# 1-Schematic_mixmult.net
KiCad netlist of a schematic drawn in EasyEDA
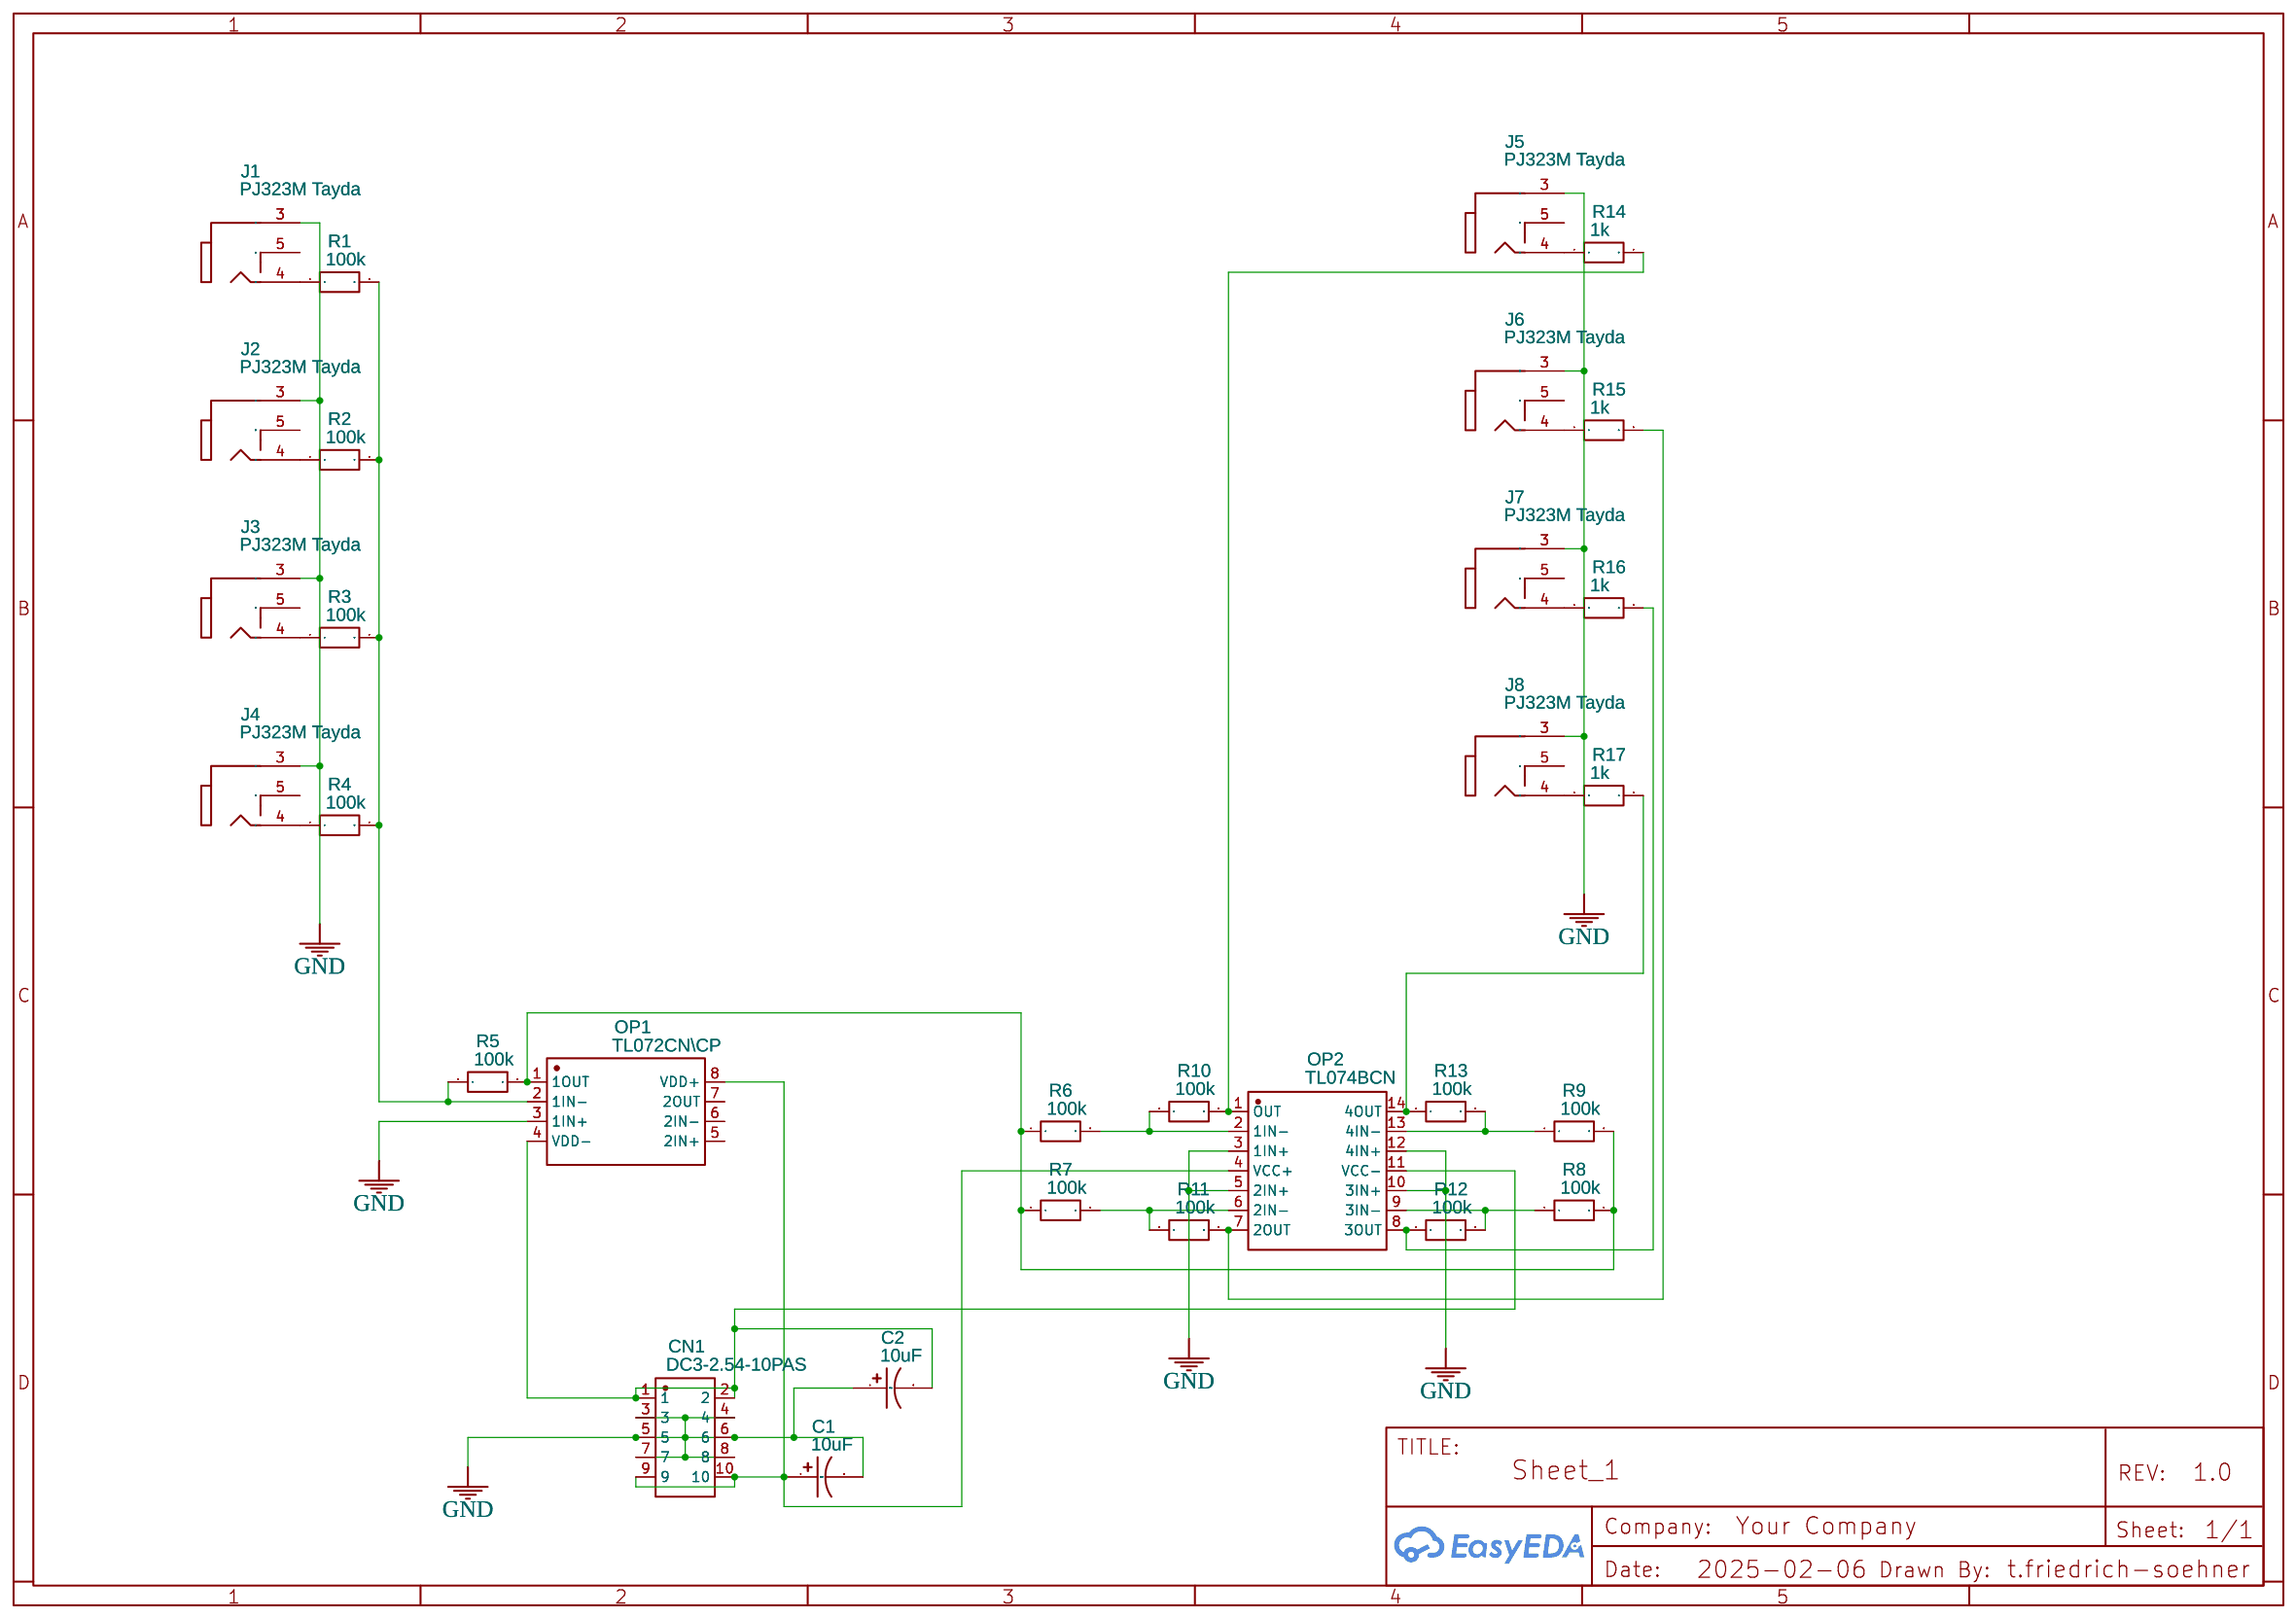
[diagram p0: schematic sheet]

(export (version "E")
  (design (tool "Eeschema 10.0.6"))
  (components
    (comp (ref "C1")
      (value "10uF")
      (fields
        (field (name "Manufacturer Part") "50MS710MEFCTZ5X7")
        (field (name "Manufacturer") "rubycon(红宝石)")
      )
      (libsource (lib "") (part "50MS710MEFCTZ5X7"))
    )
    (comp (ref "C2")
      (value "10uF")
      (fields
        (field (name "Manufacturer Part") "50MS710MEFCTZ5X7")
        (field (name "Manufacturer") "rubycon(红宝石)")
      )
      (libsource (lib "") (part "50MS710MEFCTZ5X7"))
    )
    (comp (ref "CN1")
      (value "DC3-2.54-10PAS")
      (fields (field (name "Manufacturer") "ZHOURI(洲日)"))
      (libsource (lib "") (part "DC3-2.54-10PAS"))
    )
    (comp (ref "J1") (value "PJ323M Tayda") (libsource (lib "") (part "PJ323M Tayda")))
    (comp (ref "J2") (value "PJ323M Tayda") (libsource (lib "") (part "PJ323M Tayda")))
    (comp (ref "J3") (value "PJ323M Tayda") (libsource (lib "") (part "PJ323M Tayda")))
    (comp (ref "J4") (value "PJ323M Tayda") (libsource (lib "") (part "PJ323M Tayda")))
    (comp (ref "J5") (value "PJ323M Tayda") (libsource (lib "") (part "PJ323M Tayda")))
    (comp (ref "J6") (value "PJ323M Tayda") (libsource (lib "") (part "PJ323M Tayda")))
    (comp (ref "J7") (value "PJ323M Tayda") (libsource (lib "") (part "PJ323M Tayda")))
    (comp (ref "J8") (value "PJ323M Tayda") (libsource (lib "") (part "PJ323M Tayda")))
    (comp (ref "OP1") (value "TL072CN\\CP") (libsource (lib "") (part "TL072CD")))
    (comp (ref "OP2")
      (value "TL074BCN")
      (fields (field (name "Manufacturer") "TI(德州仪器)"))
      (libsource (lib "") (part "TL074BCN"))
    )
    (comp (ref "R1") (value "100k") (libsource (lib "") (part "Res_AXIAL-0.4(1/4W)_US")))
    (comp (ref "R2") (value "100k") (libsource (lib "") (part "Res_AXIAL-0.4(1/4W)_US")))
    (comp (ref "R3") (value "100k") (libsource (lib "") (part "Res_AXIAL-0.4(1/4W)_US")))
    (comp (ref "R4") (value "100k") (libsource (lib "") (part "Res_AXIAL-0.4(1/4W)_US")))
    (comp (ref "R5") (value "100k") (libsource (lib "") (part "Res_AXIAL-0.4(1/4W)_US")))
    (comp (ref "R6") (value "100k") (libsource (lib "") (part "Res_AXIAL-0.4(1/4W)_US")))
    (comp (ref "R7") (value "100k") (libsource (lib "") (part "Res_AXIAL-0.4(1/4W)_US")))
    (comp (ref "R8") (value "100k") (libsource (lib "") (part "Res_AXIAL-0.4(1/4W)_US")))
    (comp (ref "R9") (value "100k") (libsource (lib "") (part "Res_AXIAL-0.4(1/4W)_US")))
    (comp (ref "R10") (value "100k") (libsource (lib "") (part "Res_AXIAL-0.4(1/4W)_US")))
    (comp (ref "R11") (value "100k") (libsource (lib "") (part "Res_AXIAL-0.4(1/4W)_US")))
    (comp (ref "R12") (value "100k") (libsource (lib "") (part "Res_AXIAL-0.4(1/4W)_US")))
    (comp (ref "R13") (value "100k") (libsource (lib "") (part "Res_AXIAL-0.4(1/4W)_US")))
    (comp (ref "R14") (value "1k") (libsource (lib "") (part "Res_AXIAL-0.4(1/4W)_US")))
    (comp (ref "R15") (value "1k") (libsource (lib "") (part "Res_AXIAL-0.4(1/4W)_US")))
    (comp (ref "R16") (value "1k") (libsource (lib "") (part "Res_AXIAL-0.4(1/4W)_US")))
    (comp (ref "R17") (value "1k") (libsource (lib "") (part "Res_AXIAL-0.4(1/4W)_US")))
  )
  (nets
    (net (code "1") (name "GND") (class "Default")
      (node (ref "C1") (pin "2") (pinfunction "2_2") (pintype "unspecified"))
      (node (ref "C2") (pin "1") (pinfunction "1_1") (pintype "unspecified"))
      (node (ref "CN1") (pin "3") (pinfunction "3_3") (pintype "unspecified"))
      (node (ref "CN1") (pin "4") (pinfunction "4_4") (pintype "unspecified"))
      (node (ref "CN1") (pin "5") (pinfunction "5_5") (pintype "unspecified"))
      (node (ref "CN1") (pin "6") (pinfunction "6_6") (pintype "unspecified"))
      (node (ref "CN1") (pin "7") (pinfunction "7_7") (pintype "unspecified"))
      (node (ref "CN1") (pin "8") (pinfunction "8_8") (pintype "unspecified"))
      (node (ref "J1") (pin "3") (pinfunction "3_3") (pintype "unspecified"))
      (node (ref "J2") (pin "3") (pinfunction "3_3") (pintype "unspecified"))
      (node (ref "J3") (pin "3") (pinfunction "3_3") (pintype "unspecified"))
      (node (ref "J4") (pin "3") (pinfunction "3_3") (pintype "unspecified"))
      (node (ref "J5") (pin "3") (pinfunction "3_3") (pintype "unspecified"))
      (node (ref "J6") (pin "3") (pinfunction "3_3") (pintype "unspecified"))
      (node (ref "J7") (pin "3") (pinfunction "3_3") (pintype "unspecified"))
      (node (ref "J8") (pin "3") (pinfunction "3_3") (pintype "unspecified"))
      (node (ref "OP1") (pin "3") (pinfunction "1IN+_3") (pintype "unspecified"))
      (node (ref "OP2") (pin "10") (pinfunction "3IN+_10") (pintype "unspecified"))
      (node (ref "OP2") (pin "12") (pinfunction "4IN+_12") (pintype "unspecified"))
      (node (ref "OP2") (pin "3") (pinfunction "1IN+_3") (pintype "unspecified"))
      (node (ref "OP2") (pin "5") (pinfunction "2IN+_5") (pintype "unspecified"))
    )
    (net (code "2") (name "Net-(J1-Pad4)") (class "Default")
      (node (ref "J1") (pin "4") (pinfunction "4_4") (pintype "unspecified"))
      (node (ref "R1") (pin "1") (pinfunction "1_1") (pintype "unspecified"))
    )
    (net (code "3") (name "Net-(J2-Pad4)") (class "Default")
      (node (ref "J2") (pin "4") (pinfunction "4_4") (pintype "unspecified"))
      (node (ref "R2") (pin "1") (pinfunction "1_1") (pintype "unspecified"))
    )
    (net (code "4") (name "Net-(J3-Pad4)") (class "Default")
      (node (ref "J3") (pin "4") (pinfunction "4_4") (pintype "unspecified"))
      (node (ref "R3") (pin "1") (pinfunction "1_1") (pintype "unspecified"))
    )
    (net (code "5") (name "Net-(J4-Pad4)") (class "Default")
      (node (ref "J4") (pin "4") (pinfunction "4_4") (pintype "unspecified"))
      (node (ref "R4") (pin "1") (pinfunction "1_1") (pintype "unspecified"))
    )
    (net (code "6") (name "Net-(J5-Pad4)") (class "Default")
      (node (ref "J5") (pin "4") (pinfunction "4_4") (pintype "unspecified"))
      (node (ref "R14") (pin "1") (pinfunction "1_1") (pintype "unspecified"))
    )
    (net (code "7") (name "Net-(J6-Pad4)") (class "Default")
      (node (ref "J6") (pin "4") (pinfunction "4_4") (pintype "unspecified"))
      (node (ref "R15") (pin "1") (pinfunction "1_1") (pintype "unspecified"))
    )
    (net (code "8") (name "Net-(J7-Pad4)") (class "Default")
      (node (ref "J7") (pin "4") (pinfunction "4_4") (pintype "unspecified"))
      (node (ref "R16") (pin "1") (pinfunction "1_1") (pintype "unspecified"))
    )
    (net (code "9") (name "Net-(J8-Pad4)") (class "Default")
      (node (ref "J8") (pin "4") (pinfunction "4_4") (pintype "unspecified"))
      (node (ref "R17") (pin "1") (pinfunction "1_1") (pintype "unspecified"))
    )
    (net (code "10") (name "Net-(OP1-1IN-)") (class "Default")
      (node (ref "OP1") (pin "2") (pinfunction "1IN-_2") (pintype "unspecified"))
      (node (ref "R1") (pin "2") (pinfunction "2_2") (pintype "unspecified"))
      (node (ref "R2") (pin "2") (pinfunction "2_2") (pintype "unspecified"))
      (node (ref "R3") (pin "2") (pinfunction "2_2") (pintype "unspecified"))
      (node (ref "R4") (pin "2") (pinfunction "2_2") (pintype "unspecified"))
      (node (ref "R5") (pin "1") (pinfunction "1_1") (pintype "unspecified"))
    )
    (net (code "11") (name "Net-(OP1-1OUT)") (class "Default")
      (node (ref "OP1") (pin "1") (pinfunction "1OUT_1") (pintype "unspecified"))
      (node (ref "R5") (pin "2") (pinfunction "2_2") (pintype "unspecified"))
      (node (ref "R6") (pin "1") (pinfunction "1_1") (pintype "unspecified"))
      (node (ref "R7") (pin "1") (pinfunction "1_1") (pintype "unspecified"))
      (node (ref "R8") (pin "2") (pinfunction "2_2") (pintype "unspecified"))
      (node (ref "R9") (pin "2") (pinfunction "2_2") (pintype "unspecified"))
    )
    (net (code "12") (name "Net-(OP1-VDD+)") (class "Default")
      (node (ref "C1") (pin "1") (pinfunction "1_1") (pintype "unspecified"))
      (node (ref "CN1") (pin "10") (pinfunction "10_10") (pintype "unspecified"))
      (node (ref "CN1") (pin "9") (pinfunction "9_9") (pintype "unspecified"))
      (node (ref "OP1") (pin "8") (pinfunction "VDD+_8") (pintype "unspecified"))
      (node (ref "OP2") (pin "4") (pinfunction "VCC+_4") (pintype "unspecified"))
    )
    (net (code "13") (name "Net-(OP1-VDD-)") (class "Default")
      (node (ref "C2") (pin "2") (pinfunction "2_2") (pintype "unspecified"))
      (node (ref "CN1") (pin "1") (pinfunction "1_1") (pintype "unspecified"))
      (node (ref "CN1") (pin "2") (pinfunction "2_2") (pintype "unspecified"))
      (node (ref "OP1") (pin "4") (pinfunction "VDD-_4") (pintype "unspecified"))
      (node (ref "OP2") (pin "11") (pinfunction "VCC-_11") (pintype "unspecified"))
    )
    (net (code "14") (name "Net-(OP2-1IN-)") (class "Default")
      (node (ref "OP2") (pin "2") (pinfunction "1IN-_2") (pintype "unspecified"))
      (node (ref "R10") (pin "1") (pinfunction "1_1") (pintype "unspecified"))
      (node (ref "R6") (pin "2") (pinfunction "2_2") (pintype "unspecified"))
    )
    (net (code "15") (name "Net-(OP2-2IN-)") (class "Default")
      (node (ref "OP2") (pin "6") (pinfunction "2IN-_6") (pintype "unspecified"))
      (node (ref "R11") (pin "1") (pinfunction "1_1") (pintype "unspecified"))
      (node (ref "R7") (pin "2") (pinfunction "2_2") (pintype "unspecified"))
    )
    (net (code "16") (name "Net-(OP2-2OUT)") (class "Default")
      (node (ref "OP2") (pin "7") (pinfunction "2OUT_7") (pintype "unspecified"))
      (node (ref "R11") (pin "2") (pinfunction "2_2") (pintype "unspecified"))
      (node (ref "R15") (pin "2") (pinfunction "2_2") (pintype "unspecified"))
    )
    (net (code "17") (name "Net-(OP2-3IN-)") (class "Default")
      (node (ref "OP2") (pin "9") (pinfunction "3IN-_9") (pintype "unspecified"))
      (node (ref "R12") (pin "2") (pinfunction "2_2") (pintype "unspecified"))
      (node (ref "R8") (pin "1") (pinfunction "1_1") (pintype "unspecified"))
    )
    (net (code "18") (name "Net-(OP2-3OUT)") (class "Default")
      (node (ref "OP2") (pin "8") (pinfunction "3OUT_8") (pintype "unspecified"))
      (node (ref "R12") (pin "1") (pinfunction "1_1") (pintype "unspecified"))
      (node (ref "R16") (pin "2") (pinfunction "2_2") (pintype "unspecified"))
    )
    (net (code "19") (name "Net-(OP2-4IN-)") (class "Default")
      (node (ref "OP2") (pin "13") (pinfunction "4IN-_13") (pintype "unspecified"))
      (node (ref "R13") (pin "2") (pinfunction "2_2") (pintype "unspecified"))
      (node (ref "R9") (pin "1") (pinfunction "1_1") (pintype "unspecified"))
    )
    (net (code "20") (name "Net-(OP2-4OUT)") (class "Default")
      (node (ref "OP2") (pin "14") (pinfunction "4OUT_14") (pintype "unspecified"))
      (node (ref "R13") (pin "1") (pinfunction "1_1") (pintype "unspecified"))
      (node (ref "R17") (pin "2") (pinfunction "2_2") (pintype "unspecified"))
    )
    (net (code "21") (name "Net-(OP2-OUT)") (class "Default")
      (node (ref "OP2") (pin "1") (pinfunction "OUT_1") (pintype "unspecified"))
      (node (ref "R10") (pin "2") (pinfunction "2_2") (pintype "unspecified"))
      (node (ref "R14") (pin "2") (pinfunction "2_2") (pintype "unspecified"))
    )
    (net (code "22") (name "unconnected-(J1-Pad5)") (class "Default")
      (node (ref "J1") (pin "5") (pinfunction "5_5") (pintype "unspecified"))
    )
    (net (code "23") (name "unconnected-(J2-Pad5)") (class "Default")
      (node (ref "J2") (pin "5") (pinfunction "5_5") (pintype "unspecified"))
    )
    (net (code "24") (name "unconnected-(J3-Pad5)") (class "Default")
      (node (ref "J3") (pin "5") (pinfunction "5_5") (pintype "unspecified"))
    )
    (net (code "25") (name "unconnected-(J4-Pad5)") (class "Default")
      (node (ref "J4") (pin "5") (pinfunction "5_5") (pintype "unspecified"))
    )
    (net (code "26") (name "unconnected-(J5-Pad5)") (class "Default")
      (node (ref "J5") (pin "5") (pinfunction "5_5") (pintype "unspecified"))
    )
    (net (code "27") (name "unconnected-(J6-Pad5)") (class "Default")
      (node (ref "J6") (pin "5") (pinfunction "5_5") (pintype "unspecified"))
    )
    (net (code "28") (name "unconnected-(J7-Pad5)") (class "Default")
      (node (ref "J7") (pin "5") (pinfunction "5_5") (pintype "unspecified"))
    )
    (net (code "29") (name "unconnected-(J8-Pad5)") (class "Default")
      (node (ref "J8") (pin "5") (pinfunction "5_5") (pintype "unspecified"))
    )
    (net (code "30") (name "unconnected-(OP1-2IN+-Pad5)") (class "Default")
      (node (ref "OP1") (pin "5") (pinfunction "2IN+_5") (pintype "unspecified"))
    )
    (net (code "31") (name "unconnected-(OP1-2IN--Pad6)") (class "Default")
      (node (ref "OP1") (pin "6") (pinfunction "2IN-_6") (pintype "unspecified"))
    )
    (net (code "32") (name "unconnected-(OP1-2OUT-Pad7)") (class "Default")
      (node (ref "OP1") (pin "7") (pinfunction "2OUT_7") (pintype "unspecified"))
    )
  )
)
